# psu.net
KiCad netlist of a schematic drawn in EAGLE
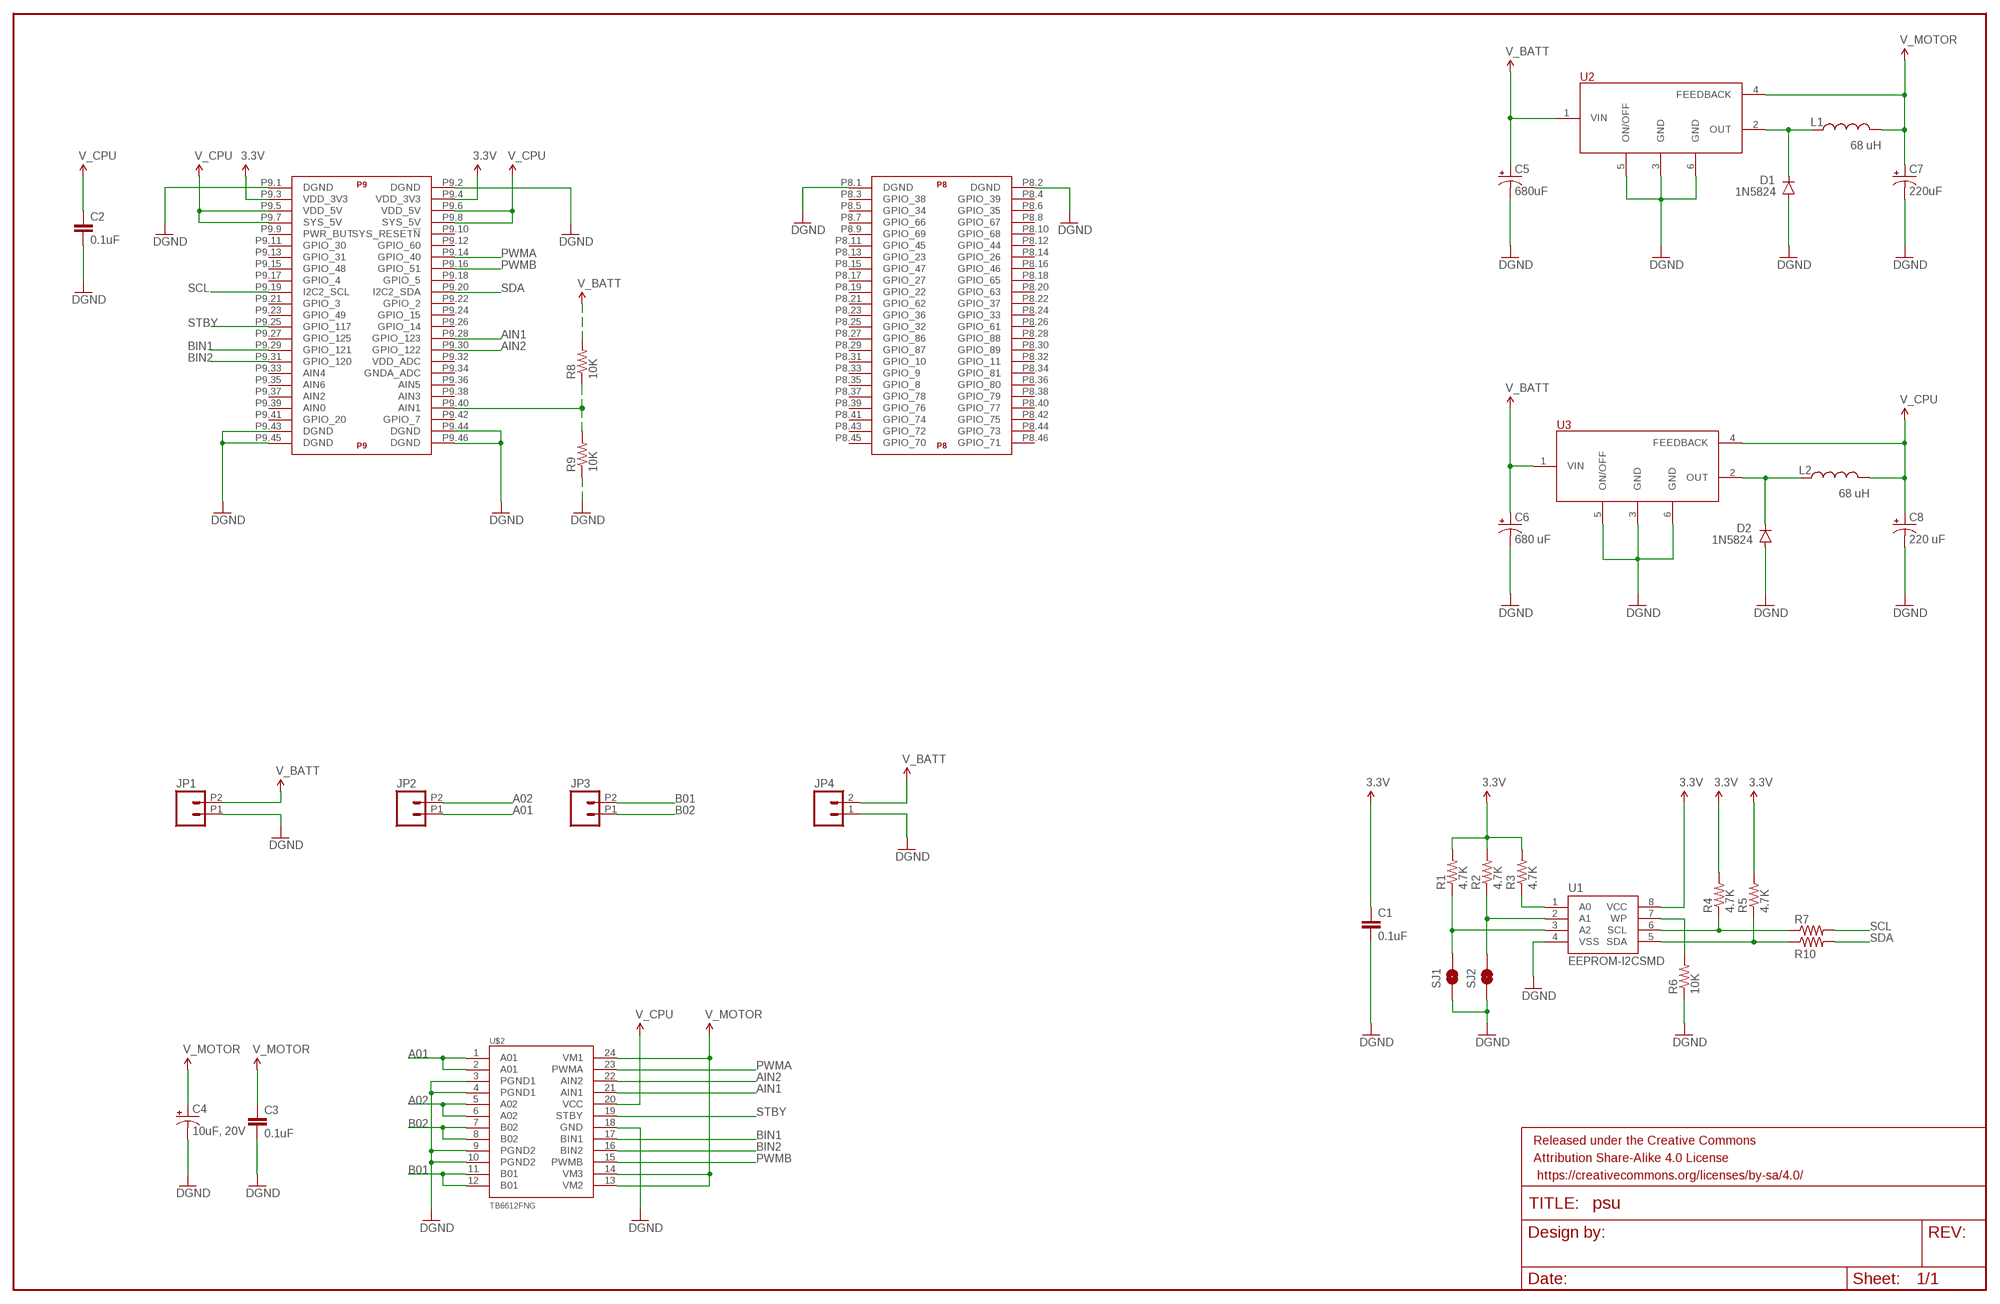
[diagram p0: schematic, sheet 1]

(export (version "E")
  (design (tool "Eeschema 10.0.6"))
  (components
    (comp (ref "C1")
      (value "0.1uF")
      (footprint "eagle-import:0603-CAP")
      (libsource (lib "eagle-import") (part "0.1UF-25V(+80/-20%)(0603)"))
    )
    (comp (ref "C2")
      (value "0.1uF")
      (footprint "eagle-import:0603-CAP")
      (libsource (lib "eagle-import") (part "0.1UF-25V(+80/-20%)(0603)"))
    )
    (comp (ref "C3")
      (value "0.1uF")
      (footprint "eagle-import:0603-CAP")
      (libsource (lib "eagle-import") (part "0.1UF-25V(+80/-20%)(0603)"))
    )
    (comp (ref "C4")
      (value "10uF, 20V")
      (footprint "eagle-import:CPOL-RADIAL-10UF-25V-KIT")
      (libsource (lib "eagle-import") (part "10UF-25V-20%(PTH)KIT"))
    )
    (comp (ref "C5")
      (value "680uF")
      (footprint "eagle-import:CPOL-RADIAL-10UF-25V")
      (libsource (lib "eagle-import") (part "CAP_POLPTH2"))
    )
    (comp (ref "C6")
      (value "680 uF")
      (footprint "eagle-import:CPOL-RADIAL-10UF-25V")
      (libsource (lib "eagle-import") (part "CAP_POLPTH2"))
    )
    (comp (ref "C7")
      (value "220uF")
      (footprint "eagle-import:CPOL-RADIAL-10UF-25V")
      (libsource (lib "eagle-import") (part "CAP_POLPTH2"))
    )
    (comp (ref "C8")
      (value "220 uF")
      (footprint "eagle-import:CPOL-RADIAL-10UF-25V")
      (libsource (lib "eagle-import") (part "CAP_POLPTH2"))
    )
    (comp (ref "D1")
      (value "1N5824")
      (footprint "eagle-import:DIODE-1N4001")
      (libsource (lib "eagle-import") (part "DIODEPTH"))
    )
    (comp (ref "D2")
      (value "1N5824")
      (footprint "eagle-import:DIODE-1N4001")
      (libsource (lib "eagle-import") (part "DIODEPTH"))
    )
    (comp (ref "FRAME2")
      (value "FRAME-LEDGER")
      (footprint "eagle-import:CREATIVE_COMMONS")
      (libsource (lib "eagle-import") (part "FRAME-LEDGER"))
    )
    (comp (ref "JP1")
      (value "M022.54MM_SCREWTERM")
      (footprint "eagle-import:1X02_2.54_SCREWTERM")
      (libsource (lib "eagle-import") (part "M022.54MM_SCREWTERM"))
    )
    (comp (ref "JP2")
      (value "M022.54MM_SCREWTERM")
      (footprint "eagle-import:1X02_2.54_SCREWTERM")
      (libsource (lib "eagle-import") (part "M022.54MM_SCREWTERM"))
    )
    (comp (ref "JP3")
      (value "M022.54MM_SCREWTERM")
      (footprint "eagle-import:1X02_2.54_SCREWTERM")
      (libsource (lib "eagle-import") (part "M022.54MM_SCREWTERM"))
    )
    (comp (ref "JP4")
      (value "M023.5MM")
      (footprint "eagle-import:SCREWTERMINAL-3.5MM-2")
      (libsource (lib "eagle-import") (part "M023.5MM"))
    )
    (comp (ref "L1")
      (value "68 uH")
      (footprint "eagle-import:0603")
      (libsource (lib "eagle-import") (part "INDUCTOR0603"))
    )
    (comp (ref "L2")
      (value "68 uH")
      (footprint "eagle-import:0603")
      (libsource (lib "eagle-import") (part "INDUCTOR0603"))
    )
    (comp (ref "R1")
      (value "4.7K")
      (footprint "eagle-import:0603-RES")
      (libsource (lib "eagle-import") (part "4.7KOHM-1/10W-1%(0603)"))
    )
    (comp (ref "R2")
      (value "4.7K")
      (footprint "eagle-import:0603-RES")
      (libsource (lib "eagle-import") (part "4.7KOHM-1/10W-1%(0603)"))
    )
    (comp (ref "R3")
      (value "4.7K")
      (footprint "eagle-import:0603-RES")
      (libsource (lib "eagle-import") (part "4.7KOHM-1/10W-1%(0603)"))
    )
    (comp (ref "R4")
      (value "4.7K")
      (footprint "eagle-import:0603-RES")
      (libsource (lib "eagle-import") (part "4.7KOHM-1/10W-1%(0603)"))
    )
    (comp (ref "R5")
      (value "4.7K")
      (footprint "eagle-import:0603-RES")
      (libsource (lib "eagle-import") (part "4.7KOHM-1/10W-1%(0603)"))
    )
    (comp (ref "R6")
      (value "10K")
      (footprint "eagle-import:0603-RES")
      (libsource (lib "eagle-import") (part "10KOHM-1/10W-1%(0603)0603"))
    )
    (comp (ref "R7")
      (value "0")
      (footprint "eagle-import:0603-RES")
      (libsource (lib "eagle-import") (part "RESISTOR0603"))
    )
    (comp (ref "R8")
      (value "10K")
      (footprint "eagle-import:0603-RES")
      (libsource (lib "eagle-import") (part "10KOHM-1/10W-1%(0603)0603"))
    )
    (comp (ref "R9")
      (value "10K")
      (footprint "eagle-import:0603-RES")
      (libsource (lib "eagle-import") (part "10KOHM-1/10W-1%(0603)0603"))
    )
    (comp (ref "R10")
      (value "0")
      (footprint "eagle-import:0603-RES")
      (libsource (lib "eagle-import") (part "RESISTOR0603"))
    )
    (comp (ref "SJ1")
      (value "JUMPER-PAD-2-NO")
      (footprint "eagle-import:PAD-JUMPER-2-NO_NO_SILK")
      (libsource (lib "eagle-import") (part "JUMPER-PAD-2-NO"))
    )
    (comp (ref "SJ2")
      (value "JUMPER-PAD-2-NO")
      (footprint "eagle-import:PAD-JUMPER-2-NO_NO_SILK")
      (libsource (lib "eagle-import") (part "JUMPER-PAD-2-NO"))
    )
    (comp (ref "U$1")
      (value "BEAGLE_BONE_BLACK_CAPE")
      (footprint "eagle-import:BEAGLE_BONE_BLACK_CAPE")
      (libsource (lib "eagle-import") (part "BEAGLE_BONE_BLACK_CAPE"))
    )
    (comp (ref "U$2")
      (value "TB6612FNG")
      (footprint "eagle-import:SSOP24")
      (libsource (lib "eagle-import") (part "TB6612FNG"))
    )
    (comp (ref "U1")
      (value "EEPROM-I2CSMD")
      (footprint "eagle-import:SO08")
      (libsource (lib "eagle-import") (part "EEPROM-I2CSMD"))
    )
    (comp (ref "U2")
      (value "LM2596")
      (footprint "eagle-import:TO-263")
      (libsource (lib "eagle-import") (part "LM2596"))
    )
    (comp (ref "U3")
      (value "LM2596")
      (footprint "eagle-import:TO-263")
      (libsource (lib "eagle-import") (part "LM2596"))
    )
  )
  (nets
    (net (code "1") (name "/A01") (class "Default")
      (node (ref "JP2") (pin "P1") (pinfunction "1_P1") (pintype "passive"))
      (node (ref "U$2") (pin "1") (pinfunction "A01_1") (pintype "bidirectional"))
      (node (ref "U$2") (pin "2") (pinfunction "A01_2") (pintype "bidirectional"))
    )
    (net (code "2") (name "/A02") (class "Default")
      (node (ref "JP2") (pin "P2") (pinfunction "2_P2") (pintype "passive"))
      (node (ref "U$2") (pin "5") (pinfunction "A02_5") (pintype "bidirectional"))
      (node (ref "U$2") (pin "6") (pinfunction "A02_6") (pintype "bidirectional"))
    )
    (net (code "3") (name "/AIN1") (class "Default")
      (node (ref "U$1") (pin "P9.28") (pinfunction "GPIO_123_P9.28") (pintype "bidirectional"))
      (node (ref "U$2") (pin "21") (pinfunction "AIN1_21") (pintype "bidirectional"))
    )
    (net (code "4") (name "/AIN2") (class "Default")
      (node (ref "U$1") (pin "P9.30") (pinfunction "GPIO_122_P9.30") (pintype "bidirectional"))
      (node (ref "U$2") (pin "22") (pinfunction "AIN2_22") (pintype "bidirectional"))
    )
    (net (code "5") (name "/B01") (class "Default")
      (node (ref "JP3") (pin "P2") (pinfunction "2_P2") (pintype "passive"))
      (node (ref "U$2") (pin "11") (pinfunction "B01_11") (pintype "bidirectional"))
      (node (ref "U$2") (pin "12") (pinfunction "B01_12") (pintype "bidirectional"))
    )
    (net (code "6") (name "/B02") (class "Default")
      (node (ref "JP3") (pin "P1") (pinfunction "1_P1") (pintype "passive"))
      (node (ref "U$2") (pin "7") (pinfunction "B02_7") (pintype "bidirectional"))
      (node (ref "U$2") (pin "8") (pinfunction "B02_8") (pintype "bidirectional"))
    )
    (net (code "7") (name "/BIN1") (class "Default")
      (node (ref "U$1") (pin "P9.29") (pinfunction "GPIO_121_P9.29") (pintype "bidirectional"))
      (node (ref "U$2") (pin "17") (pinfunction "BIN1_17") (pintype "bidirectional"))
    )
    (net (code "8") (name "/BIN2") (class "Default")
      (node (ref "U$1") (pin "P9.31") (pinfunction "GPIO_120_P9.31") (pintype "bidirectional"))
      (node (ref "U$2") (pin "16") (pinfunction "BIN2_16") (pintype "bidirectional"))
    )
    (net (code "9") (name "/PWMA") (class "Default")
      (node (ref "U$1") (pin "P9.14") (pinfunction "GPIO_40_P9.14") (pintype "bidirectional"))
      (node (ref "U$2") (pin "23") (pinfunction "PWMA_23") (pintype "bidirectional"))
    )
    (net (code "10") (name "/PWMB") (class "Default")
      (node (ref "U$1") (pin "P9.16") (pinfunction "GPIO_51_P9.16") (pintype "bidirectional"))
      (node (ref "U$2") (pin "15") (pinfunction "PWMB_15") (pintype "bidirectional"))
    )
    (net (code "11") (name "/SCL") (class "Default")
      (node (ref "R7") (pin "2") (pinfunction "2_2") (pintype "passive"))
      (node (ref "U$1") (pin "P9.19") (pinfunction "I2C2_SCL_P9.19") (pintype "bidirectional"))
    )
    (net (code "12") (name "/SDA") (class "Default")
      (node (ref "R10") (pin "2") (pinfunction "2_2") (pintype "passive"))
      (node (ref "U$1") (pin "P9.20") (pinfunction "I2C2_SDA_P9.20") (pintype "bidirectional"))
    )
    (net (code "13") (name "/STBY") (class "Default")
      (node (ref "U$1") (pin "P9.25") (pinfunction "GPIO_117_P9.25") (pintype "bidirectional"))
      (node (ref "U$2") (pin "19") (pinfunction "STBY_19") (pintype "bidirectional"))
    )
    (net (code "14") (name "3.3V") (class "Default")
      (node (ref "C1") (pin "1") (pinfunction "1_1") (pintype "passive"))
      (node (ref "R1") (pin "2") (pinfunction "2_2") (pintype "passive"))
      (node (ref "R2") (pin "2") (pinfunction "2_2") (pintype "passive"))
      (node (ref "R3") (pin "2") (pinfunction "2_2") (pintype "passive"))
      (node (ref "R4") (pin "2") (pinfunction "2_2") (pintype "passive"))
      (node (ref "R5") (pin "2") (pinfunction "2_2") (pintype "passive"))
      (node (ref "U$1") (pin "P9.3") (pinfunction "VDD_3V3_P9.3") (pintype "bidirectional"))
      (node (ref "U$1") (pin "P9.4") (pinfunction "VDD_3V3_P9.4") (pintype "bidirectional"))
      (node (ref "U1") (pin "8") (pinfunction "VCC_8") (pintype "power_in"))
    )
    (net (code "15") (name "DGND") (class "Default")
      (node (ref "C1") (pin "2") (pinfunction "2_2") (pintype "passive"))
      (node (ref "C2") (pin "2") (pinfunction "2_2") (pintype "passive"))
      (node (ref "C3") (pin "2") (pinfunction "2_2") (pintype "passive"))
      (node (ref "C4") (pin "2") (pinfunction "-_2") (pintype "passive"))
      (node (ref "C5") (pin "2") (pinfunction "-_2") (pintype "passive"))
      (node (ref "C6") (pin "2") (pinfunction "-_2") (pintype "passive"))
      (node (ref "C7") (pin "2") (pinfunction "-_2") (pintype "passive"))
      (node (ref "C8") (pin "2") (pinfunction "-_2") (pintype "passive"))
      (node (ref "D1") (pin "A") (pinfunction "A_A") (pintype "passive"))
      (node (ref "D2") (pin "A") (pinfunction "A_A") (pintype "passive"))
      (node (ref "JP1") (pin "P1") (pinfunction "1_P1") (pintype "passive"))
      (node (ref "JP4") (pin "1") (pinfunction "1_1") (pintype "passive"))
      (node (ref "R6") (pin "1") (pinfunction "1_1") (pintype "passive"))
      (node (ref "R9") (pin "1") (pinfunction "1_1") (pintype "passive"))
      (node (ref "SJ1") (pin "1") (pinfunction "1_1") (pintype "passive"))
      (node (ref "SJ2") (pin "1") (pinfunction "1_1") (pintype "passive"))
      (node (ref "U$1") (pin "P8.1") (pinfunction "DGND_P8.1") (pintype "bidirectional"))
      (node (ref "U$1") (pin "P8.2") (pinfunction "DGND_P8.2") (pintype "bidirectional"))
      (node (ref "U$1") (pin "P9.1") (pinfunction "DGND_P9.1") (pintype "bidirectional"))
      (node (ref "U$1") (pin "P9.2") (pinfunction "DGND_P9.2") (pintype "bidirectional"))
      (node (ref "U$1") (pin "P9.43") (pinfunction "DGND_P9.43") (pintype "bidirectional"))
      (node (ref "U$1") (pin "P9.44") (pinfunction "DGND_P9.44") (pintype "bidirectional"))
      (node (ref "U$1") (pin "P9.45") (pinfunction "DGND_P9.45") (pintype "bidirectional"))
      (node (ref "U$1") (pin "P9.46") (pinfunction "DGND_P9.46") (pintype "bidirectional"))
      (node (ref "U$2") (pin "10") (pinfunction "PGND2_10") (pintype "bidirectional"))
      (node (ref "U$2") (pin "18") (pinfunction "GND_18") (pintype "bidirectional"))
      (node (ref "U$2") (pin "3") (pinfunction "PGND1_3") (pintype "bidirectional"))
      (node (ref "U$2") (pin "4") (pinfunction "PGND1_4") (pintype "bidirectional"))
      (node (ref "U$2") (pin "9") (pinfunction "PGND2_9") (pintype "bidirectional"))
      (node (ref "U1") (pin "4") (pinfunction "VSS_4") (pintype "power_in"))
      (node (ref "U2") (pin "3") (pinfunction "GND_3") (pintype "power_in"))
      (node (ref "U2") (pin "5") (pinfunction "ON/OFF_5") (pintype "input"))
      (node (ref "U2") (pin "6") (pinfunction "GND_6") (pintype "power_in"))
      (node (ref "U3") (pin "3") (pinfunction "GND_3") (pintype "power_in"))
      (node (ref "U3") (pin "5") (pinfunction "ON/OFF_5") (pintype "input"))
      (node (ref "U3") (pin "6") (pinfunction "GND_6") (pintype "power_in"))
    )
    (net (code "16") (name "Net-(U$1B-AIN1)") (class "Default")
      (node (ref "R8") (pin "1") (pinfunction "1_1") (pintype "passive"))
      (node (ref "R9") (pin "2") (pinfunction "2_2") (pintype "passive"))
      (node (ref "U$1") (pin "P9.40") (pinfunction "AIN1_P9.40") (pintype "bidirectional"))
    )
    (net (code "17") (name "Net-(U1-A0)") (class "Default")
      (node (ref "R3") (pin "1") (pinfunction "1_1") (pintype "passive"))
      (node (ref "U1") (pin "1") (pinfunction "A0_1") (pintype "bidirectional"))
    )
    (net (code "18") (name "Net-(U1-A1)") (class "Default")
      (node (ref "R2") (pin "1") (pinfunction "1_1") (pintype "passive"))
      (node (ref "SJ2") (pin "2") (pinfunction "2_2") (pintype "passive"))
      (node (ref "U1") (pin "2") (pinfunction "A1_2") (pintype "bidirectional"))
    )
    (net (code "19") (name "Net-(U1-A2)") (class "Default")
      (node (ref "R1") (pin "1") (pinfunction "1_1") (pintype "passive"))
      (node (ref "SJ1") (pin "2") (pinfunction "2_2") (pintype "passive"))
      (node (ref "U1") (pin "3") (pinfunction "A2_3") (pintype "bidirectional"))
    )
    (net (code "20") (name "Net-(U1-SCL)") (class "Default")
      (node (ref "R4") (pin "1") (pinfunction "1_1") (pintype "passive"))
      (node (ref "R7") (pin "1") (pinfunction "1_1") (pintype "passive"))
      (node (ref "U1") (pin "6") (pinfunction "SCL_6") (pintype "bidirectional"))
    )
    (net (code "21") (name "Net-(U1-SDA)") (class "Default")
      (node (ref "R10") (pin "1") (pinfunction "1_1") (pintype "passive"))
      (node (ref "R5") (pin "1") (pinfunction "1_1") (pintype "passive"))
      (node (ref "U1") (pin "5") (pinfunction "SDA_5") (pintype "bidirectional"))
    )
    (net (code "22") (name "Net-(U1-WP)") (class "Default")
      (node (ref "R6") (pin "2") (pinfunction "2_2") (pintype "passive"))
      (node (ref "U1") (pin "7") (pinfunction "WP_7") (pintype "bidirectional"))
    )
    (net (code "23") (name "Net-(U2-OUT)") (class "Default")
      (node (ref "D1") (pin "C") (pinfunction "C_C") (pintype "passive"))
      (node (ref "L1") (pin "1") (pinfunction "1_1") (pintype "passive"))
      (node (ref "U2") (pin "2") (pinfunction "OUT_2") (pintype "power_in"))
    )
    (net (code "24") (name "Net-(U3-OUT)") (class "Default")
      (node (ref "D2") (pin "C") (pinfunction "C_C") (pintype "passive"))
      (node (ref "L2") (pin "1") (pinfunction "1_1") (pintype "passive"))
      (node (ref "U3") (pin "2") (pinfunction "OUT_2") (pintype "power_in"))
    )
    (net (code "25") (name "V_BATT") (class "Default")
      (node (ref "C5") (pin "1") (pinfunction "+_1") (pintype "passive"))
      (node (ref "C6") (pin "1") (pinfunction "+_1") (pintype "passive"))
      (node (ref "JP1") (pin "P2") (pinfunction "2_P2") (pintype "passive"))
      (node (ref "JP4") (pin "2") (pinfunction "2_2") (pintype "passive"))
      (node (ref "R8") (pin "2") (pinfunction "2_2") (pintype "passive"))
      (node (ref "U2") (pin "1") (pinfunction "VIN_1") (pintype "power_in"))
      (node (ref "U3") (pin "1") (pinfunction "VIN_1") (pintype "power_in"))
    )
    (net (code "26") (name "V_CPU") (class "Default")
      (node (ref "C2") (pin "1") (pinfunction "1_1") (pintype "passive"))
      (node (ref "C8") (pin "1") (pinfunction "+_1") (pintype "passive"))
      (node (ref "L2") (pin "2") (pinfunction "2_2") (pintype "passive"))
      (node (ref "U$1") (pin "P9.5") (pinfunction "VDD_5V_P9.5") (pintype "bidirectional"))
      (node (ref "U$1") (pin "P9.6") (pinfunction "VDD_5V_P9.6") (pintype "bidirectional"))
      (node (ref "U$1") (pin "P9.7") (pinfunction "SYS_5V_P9.7") (pintype "bidirectional"))
      (node (ref "U$1") (pin "P9.8") (pinfunction "SYS_5V_P9.8") (pintype "bidirectional"))
      (node (ref "U$2") (pin "20") (pinfunction "VCC_20") (pintype "bidirectional"))
      (node (ref "U3") (pin "4") (pinfunction "FEEDBACK_4") (pintype "output"))
    )
    (net (code "27") (name "V_MOTOR") (class "Default")
      (node (ref "C3") (pin "1") (pinfunction "1_1") (pintype "passive"))
      (node (ref "C4") (pin "1") (pinfunction "+_1") (pintype "passive"))
      (node (ref "C7") (pin "1") (pinfunction "+_1") (pintype "passive"))
      (node (ref "L1") (pin "2") (pinfunction "2_2") (pintype "passive"))
      (node (ref "U$2") (pin "13") (pinfunction "VM2_13") (pintype "bidirectional"))
      (node (ref "U$2") (pin "14") (pinfunction "VM3_14") (pintype "bidirectional"))
      (node (ref "U$2") (pin "24") (pinfunction "VM1_24") (pintype "bidirectional"))
      (node (ref "U2") (pin "4") (pinfunction "FEEDBACK_4") (pintype "output"))
    )
    (net (code "28") (name "unconnected-(U$1A-GPIO_8-PadP8.35)") (class "Default")
      (node (ref "U$1") (pin "P8.35") (pinfunction "GPIO_8_P8.35") (pintype "bidirectional"))
    )
    (net (code "29") (name "unconnected-(U$1A-GPIO_9-PadP8.33)") (class "Default")
      (node (ref "U$1") (pin "P8.33") (pinfunction "GPIO_9_P8.33") (pintype "bidirectional"))
    )
    (net (code "30") (name "unconnected-(U$1A-GPIO_10-PadP8.31)") (class "Default")
      (node (ref "U$1") (pin "P8.31") (pinfunction "GPIO_10_P8.31") (pintype "bidirectional"))
    )
    (net (code "31") (name "unconnected-(U$1A-GPIO_11-PadP8.32)") (class "Default")
      (node (ref "U$1") (pin "P8.32") (pinfunction "GPIO_11_P8.32") (pintype "bidirectional"))
    )
    (net (code "32") (name "unconnected-(U$1A-GPIO_22-PadP8.19)") (class "Default")
      (node (ref "U$1") (pin "P8.19") (pinfunction "GPIO_22_P8.19") (pintype "bidirectional"))
    )
    (net (code "33") (name "unconnected-(U$1A-GPIO_23-PadP8.13)") (class "Default")
      (node (ref "U$1") (pin "P8.13") (pinfunction "GPIO_23_P8.13") (pintype "bidirectional"))
    )
    (net (code "34") (name "unconnected-(U$1A-GPIO_26-PadP8.14)") (class "Default")
      (node (ref "U$1") (pin "P8.14") (pinfunction "GPIO_26_P8.14") (pintype "bidirectional"))
    )
    (net (code "35") (name "unconnected-(U$1A-GPIO_27-PadP8.17)") (class "Default")
      (node (ref "U$1") (pin "P8.17") (pinfunction "GPIO_27_P8.17") (pintype "bidirectional"))
    )
    (net (code "36") (name "unconnected-(U$1A-GPIO_32-PadP8.25)") (class "Default")
      (node (ref "U$1") (pin "P8.25") (pinfunction "GPIO_32_P8.25") (pintype "bidirectional"))
    )
    (net (code "37") (name "unconnected-(U$1A-GPIO_33-PadP8.24)") (class "Default")
      (node (ref "U$1") (pin "P8.24") (pinfunction "GPIO_33_P8.24") (pintype "bidirectional"))
    )
    (net (code "38") (name "unconnected-(U$1A-GPIO_34-PadP8.5)") (class "Default")
      (node (ref "U$1") (pin "P8.5") (pinfunction "GPIO_34_P8.5") (pintype "bidirectional"))
    )
    (net (code "39") (name "unconnected-(U$1A-GPIO_35-PadP8.6)") (class "Default")
      (node (ref "U$1") (pin "P8.6") (pinfunction "GPIO_35_P8.6") (pintype "bidirectional"))
    )
    (net (code "40") (name "unconnected-(U$1A-GPIO_36-PadP8.23)") (class "Default")
      (node (ref "U$1") (pin "P8.23") (pinfunction "GPIO_36_P8.23") (pintype "bidirectional"))
    )
    (net (code "41") (name "unconnected-(U$1A-GPIO_37-PadP8.22)") (class "Default")
      (node (ref "U$1") (pin "P8.22") (pinfunction "GPIO_37_P8.22") (pintype "bidirectional"))
    )
    (net (code "42") (name "unconnected-(U$1A-GPIO_38-PadP8.3)") (class "Default")
      (node (ref "U$1") (pin "P8.3") (pinfunction "GPIO_38_P8.3") (pintype "bidirectional"))
    )
    (net (code "43") (name "unconnected-(U$1A-GPIO_39-PadP8.4)") (class "Default")
      (node (ref "U$1") (pin "P8.4") (pinfunction "GPIO_39_P8.4") (pintype "bidirectional"))
    )
    (net (code "44") (name "unconnected-(U$1A-GPIO_44-PadP8.12)") (class "Default")
      (node (ref "U$1") (pin "P8.12") (pinfunction "GPIO_44_P8.12") (pintype "bidirectional"))
    )
    (net (code "45") (name "unconnected-(U$1A-GPIO_45-PadP8.11)") (class "Default")
      (node (ref "U$1") (pin "P8.11") (pinfunction "GPIO_45_P8.11") (pintype "bidirectional"))
    )
    (net (code "46") (name "unconnected-(U$1A-GPIO_46-PadP8.16)") (class "Default")
      (node (ref "U$1") (pin "P8.16") (pinfunction "GPIO_46_P8.16") (pintype "bidirectional"))
    )
    (net (code "47") (name "unconnected-(U$1A-GPIO_47-PadP8.15)") (class "Default")
      (node (ref "U$1") (pin "P8.15") (pinfunction "GPIO_47_P8.15") (pintype "bidirectional"))
    )
    (net (code "48") (name "unconnected-(U$1A-GPIO_61-PadP8.26)") (class "Default")
      (node (ref "U$1") (pin "P8.26") (pinfunction "GPIO_61_P8.26") (pintype "bidirectional"))
    )
    (net (code "49") (name "unconnected-(U$1A-GPIO_62-PadP8.21)") (class "Default")
      (node (ref "U$1") (pin "P8.21") (pinfunction "GPIO_62_P8.21") (pintype "bidirectional"))
    )
    (net (code "50") (name "unconnected-(U$1A-GPIO_63-PadP8.20)") (class "Default")
      (node (ref "U$1") (pin "P8.20") (pinfunction "GPIO_63_P8.20") (pintype "bidirectional"))
    )
    (net (code "51") (name "unconnected-(U$1A-GPIO_65-PadP8.18)") (class "Default")
      (node (ref "U$1") (pin "P8.18") (pinfunction "GPIO_65_P8.18") (pintype "bidirectional"))
    )
    (net (code "52") (name "unconnected-(U$1A-GPIO_66-PadP8.7)") (class "Default")
      (node (ref "U$1") (pin "P8.7") (pinfunction "GPIO_66_P8.7") (pintype "bidirectional"))
    )
    (net (code "53") (name "unconnected-(U$1A-GPIO_67-PadP8.8)") (class "Default")
      (node (ref "U$1") (pin "P8.8") (pinfunction "GPIO_67_P8.8") (pintype "bidirectional"))
    )
    (net (code "54") (name "unconnected-(U$1A-GPIO_68-PadP8.10)") (class "Default")
      (node (ref "U$1") (pin "P8.10") (pinfunction "GPIO_68_P8.10") (pintype "bidirectional"))
    )
    (net (code "55") (name "unconnected-(U$1A-GPIO_69-PadP8.9)") (class "Default")
      (node (ref "U$1") (pin "P8.9") (pinfunction "GPIO_69_P8.9") (pintype "bidirectional"))
    )
    (net (code "56") (name "unconnected-(U$1A-GPIO_70-PadP8.45)") (class "Default")
      (node (ref "U$1") (pin "P8.45") (pinfunction "GPIO_70_P8.45") (pintype "bidirectional"))
    )
    (net (code "57") (name "unconnected-(U$1A-GPIO_71-PadP8.46)") (class "Default")
      (node (ref "U$1") (pin "P8.46") (pinfunction "GPIO_71_P8.46") (pintype "bidirectional"))
    )
    (net (code "58") (name "unconnected-(U$1A-GPIO_72-PadP8.43)") (class "Default")
      (node (ref "U$1") (pin "P8.43") (pinfunction "GPIO_72_P8.43") (pintype "bidirectional"))
    )
    (net (code "59") (name "unconnected-(U$1A-GPIO_73-PadP8.44)") (class "Default")
      (node (ref "U$1") (pin "P8.44") (pinfunction "GPIO_73_P8.44") (pintype "bidirectional"))
    )
    (net (code "60") (name "unconnected-(U$1A-GPIO_74-PadP8.41)") (class "Default")
      (node (ref "U$1") (pin "P8.41") (pinfunction "GPIO_74_P8.41") (pintype "bidirectional"))
    )
    (net (code "61") (name "unconnected-(U$1A-GPIO_75-PadP8.42)") (class "Default")
      (node (ref "U$1") (pin "P8.42") (pinfunction "GPIO_75_P8.42") (pintype "bidirectional"))
    )
    (net (code "62") (name "unconnected-(U$1A-GPIO_76-PadP8.39)") (class "Default")
      (node (ref "U$1") (pin "P8.39") (pinfunction "GPIO_76_P8.39") (pintype "bidirectional"))
    )
    (net (code "63") (name "unconnected-(U$1A-GPIO_77-PadP8.40)") (class "Default")
      (node (ref "U$1") (pin "P8.40") (pinfunction "GPIO_77_P8.40") (pintype "bidirectional"))
    )
    (net (code "64") (name "unconnected-(U$1A-GPIO_78-PadP8.37)") (class "Default")
      (node (ref "U$1") (pin "P8.37") (pinfunction "GPIO_78_P8.37") (pintype "bidirectional"))
    )
    (net (code "65") (name "unconnected-(U$1A-GPIO_79-PadP8.38)") (class "Default")
      (node (ref "U$1") (pin "P8.38") (pinfunction "GPIO_79_P8.38") (pintype "bidirectional"))
    )
    (net (code "66") (name "unconnected-(U$1A-GPIO_80-PadP8.36)") (class "Default")
      (node (ref "U$1") (pin "P8.36") (pinfunction "GPIO_80_P8.36") (pintype "bidirectional"))
    )
    (net (code "67") (name "unconnected-(U$1A-GPIO_81-PadP8.34)") (class "Default")
      (node (ref "U$1") (pin "P8.34") (pinfunction "GPIO_81_P8.34") (pintype "bidirectional"))
    )
    (net (code "68") (name "unconnected-(U$1A-GPIO_86-PadP8.27)") (class "Default")
      (node (ref "U$1") (pin "P8.27") (pinfunction "GPIO_86_P8.27") (pintype "bidirectional"))
    )
    (net (code "69") (name "unconnected-(U$1A-GPIO_87-PadP8.29)") (class "Default")
      (node (ref "U$1") (pin "P8.29") (pinfunction "GPIO_87_P8.29") (pintype "bidirectional"))
    )
    (net (code "70") (name "unconnected-(U$1A-GPIO_88-PadP8.28)") (class "Default")
      (node (ref "U$1") (pin "P8.28") (pinfunction "GPIO_88_P8.28") (pintype "bidirectional"))
    )
    (net (code "71") (name "unconnected-(U$1A-GPIO_89-PadP8.30)") (class "Default")
      (node (ref "U$1") (pin "P8.30") (pinfunction "GPIO_89_P8.30") (pintype "bidirectional"))
    )
    (net (code "72") (name "unconnected-(U$1B-AIN0-PadP9.39)") (class "Default")
      (node (ref "U$1") (pin "P9.39") (pinfunction "AIN0_P9.39") (pintype "bidirectional"))
    )
    (net (code "73") (name "unconnected-(U$1B-AIN2-PadP9.37)") (class "Default")
      (node (ref "U$1") (pin "P9.37") (pinfunction "AIN2_P9.37") (pintype "bidirectional"))
    )
    (net (code "74") (name "unconnected-(U$1B-AIN3-PadP9.38)") (class "Default")
      (node (ref "U$1") (pin "P9.38") (pinfunction "AIN3_P9.38") (pintype "bidirectional"))
    )
    (net (code "75") (name "unconnected-(U$1B-AIN4-PadP9.33)") (class "Default")
      (node (ref "U$1") (pin "P9.33") (pinfunction "AIN4_P9.33") (pintype "bidirectional"))
    )
    (net (code "76") (name "unconnected-(U$1B-AIN5-PadP9.36)") (class "Default")
      (node (ref "U$1") (pin "P9.36") (pinfunction "AIN5_P9.36") (pintype "bidirectional"))
    )
    (net (code "77") (name "unconnected-(U$1B-AIN6-PadP9.35)") (class "Default")
      (node (ref "U$1") (pin "P9.35") (pinfunction "AIN6_P9.35") (pintype "bidirectional"))
    )
    (net (code "78") (name "unconnected-(U$1B-GNDA_ADC-PadP9.34)") (class "Default")
      (node (ref "U$1") (pin "P9.34") (pinfunction "GNDA_ADC_P9.34") (pintype "bidirectional"))
    )
    (net (code "79") (name "unconnected-(U$1B-GPIO_2-PadP9.22)") (class "Default")
      (node (ref "U$1") (pin "P9.22") (pinfunction "GPIO_2_P9.22") (pintype "bidirectional"))
    )
    (net (code "80") (name "unconnected-(U$1B-GPIO_3-PadP9.21)") (class "Default")
      (node (ref "U$1") (pin "P9.21") (pinfunction "GPIO_3_P9.21") (pintype "bidirectional"))
    )
    (net (code "81") (name "unconnected-(U$1B-GPIO_4-PadP9.17)") (class "Default")
      (node (ref "U$1") (pin "P9.17") (pinfunction "GPIO_4_P9.17") (pintype "bidirectional"))
    )
    (net (code "82") (name "unconnected-(U$1B-GPIO_5-PadP9.18)") (class "Default")
      (node (ref "U$1") (pin "P9.18") (pinfunction "GPIO_5_P9.18") (pintype "bidirectional"))
    )
    (net (code "83") (name "unconnected-(U$1B-GPIO_7-PadP9.42)") (class "Default")
      (node (ref "U$1") (pin "P9.42") (pinfunction "GPIO_7_P9.42") (pintype "bidirectional"))
    )
    (net (code "84") (name "unconnected-(U$1B-GPIO_14-PadP9.26)") (class "Default")
      (node (ref "U$1") (pin "P9.26") (pinfunction "GPIO_14_P9.26") (pintype "bidirectional"))
    )
    (net (code "85") (name "unconnected-(U$1B-GPIO_15-PadP9.24)") (class "Default")
      (node (ref "U$1") (pin "P9.24") (pinfunction "GPIO_15_P9.24") (pintype "bidirectional"))
    )
    (net (code "86") (name "unconnected-(U$1B-GPIO_20-PadP9.41)") (class "Default")
      (node (ref "U$1") (pin "P9.41") (pinfunction "GPIO_20_P9.41") (pintype "bidirectional"))
    )
    (net (code "87") (name "unconnected-(U$1B-GPIO_30-PadP9.11)") (class "Default")
      (node (ref "U$1") (pin "P9.11") (pinfunction "GPIO_30_P9.11") (pintype "bidirectional"))
    )
    (net (code "88") (name "unconnected-(U$1B-GPIO_31-PadP9.13)") (class "Default")
      (node (ref "U$1") (pin "P9.13") (pinfunction "GPIO_31_P9.13") (pintype "bidirectional"))
    )
    (net (code "89") (name "unconnected-(U$1B-GPIO_48-PadP9.15)") (class "Default")
      (node (ref "U$1") (pin "P9.15") (pinfunction "GPIO_48_P9.15") (pintype "bidirectional"))
    )
    (net (code "90") (name "unconnected-(U$1B-GPIO_49-PadP9.23)") (class "Default")
      (node (ref "U$1") (pin "P9.23") (pinfunction "GPIO_49_P9.23") (pintype "bidirectional"))
    )
    (net (code "91") (name "unconnected-(U$1B-GPIO_60-PadP9.12)") (class "Default")
      (node (ref "U$1") (pin "P9.12") (pinfunction "GPIO_60_P9.12") (pintype "bidirectional"))
    )
    (net (code "92") (name "unconnected-(U$1B-GPIO_125-PadP9.27)") (class "Default")
      (node (ref "U$1") (pin "P9.27") (pinfunction "GPIO_125_P9.27") (pintype "bidirectional"))
    )
    (net (code "93") (name "unconnected-(U$1B-PWR_BUT-PadP9.9)") (class "Default")
      (node (ref "U$1") (pin "P9.9") (pinfunction "PWR_BUT_P9.9") (pintype "bidirectional"))
    )
    (net (code "94") (name "unconnected-(U$1B-SYS_RESET~{N}-PadP9.10)") (class "Default")
      (node (ref "U$1") (pin "P9.10") (pinfunction "SYS_RESET~{N}_P9.10") (pintype "bidirectional"))
    )
    (net (code "95") (name "unconnected-(U$1B-VDD_ADC-PadP9.32)") (class "Default")
      (node (ref "U$1") (pin "P9.32") (pinfunction "VDD_ADC_P9.32") (pintype "bidirectional"))
    )
  )
)
